# IC_VCE.net
KiCad netlist of a schematic drawn in Altium Designer
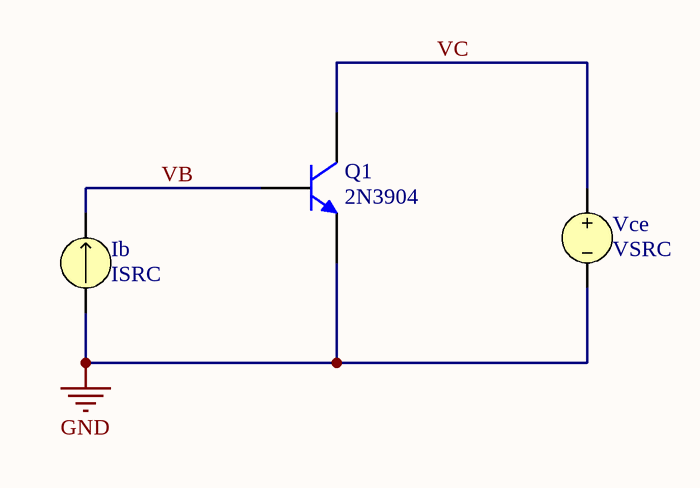
[diagram p0: IC_VCE.SchDoc]

(export (version "E")
  (design (tool "Eeschema 10.0.6"))
  (components
    (comp (ref "Ib")
      (value "ISRC")
      (description "Current Source")
      (fields (field (name "PUBLISHER") "Altium Limited"))
      (libsource (lib "Simulation Sources") (part "ISRC"))
    )
    (comp (ref "Q1")
      (value "2N3904")
      (footprint "TO-92A")
      (description "NPN General Purpose Amplifier")
      (fields (field (name "PUBLISHER") "Altium Limited"))
      (libsource (lib "Miscellaneous Devices") (part "2N3904"))
    )
    (comp (ref "Vce")
      (value "VSRC")
      (description "Voltage Source")
      (fields (field (name "PUBLISHER") "Altium Limited"))
      (libsource (lib "Simulation Sources") (part "VSRC"))
    )
  )
  (nets
    (net (code "1") (name "/VB") (class "Default")
      (node (ref "Ib") (pin "2") (pinfunction "2_2") (pintype "passive"))
      (node (ref "Q1") (pin "2") (pinfunction "B_2") (pintype "passive"))
    )
    (net (code "2") (name "/VC") (class "Default")
      (node (ref "Q1") (pin "3") (pinfunction "C_3") (pintype "passive"))
      (node (ref "Vce") (pin "1") (pinfunction "1_1") (pintype "passive"))
    )
    (net (code "3") (name "GND") (class "Default")
      (node (ref "Ib") (pin "1") (pinfunction "1_1") (pintype "passive"))
      (node (ref "Q1") (pin "1") (pinfunction "E_1") (pintype "passive"))
      (node (ref "Vce") (pin "2") (pinfunction "2_2") (pintype "passive"))
    )
  )
)
